# legacy-usr_interface.net
KiCad netlist of a schematic drawn in Altium Designer
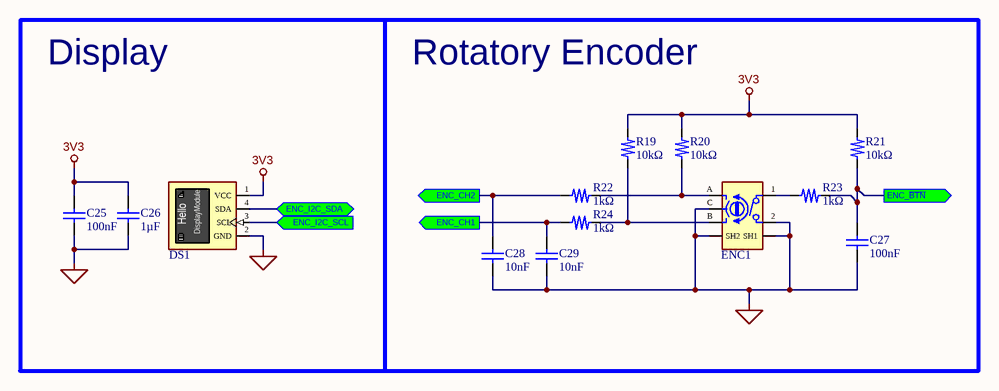
[diagram p0: legacy-usr_interface.SchDoc]

(export (version "E")
  (design (tool "Eeschema 10.0.6"))
  (components
    (comp (ref "C25")
      (value "100nF")
      (footprint "CAPC2012X135N")
      (description "50V 100nF X7R ±10% 0805 Multilayer Ceramic Capacitors MLCC - SMD/SMT ROHS")
      (fields
        (field (name "MANUFACTURER") "YAGEO")
        (field (name "MANUFACTURER PART NUMBER") "CC0805KRX7R9BB104")
      )
      (libsource (lib "Capacitors") (part "CC0805KRX7R9BB104"))
    )
    (comp (ref "C26")
      (value "1µF")
      (footprint "CAPC2012X135N")
      (description "50V 1uF X7R ±10% 0805 Multilayer Ceramic Capacitors MLCC - SMD/SMT ROHS")
      (fields
        (field (name "MANUFACTURER") "Samsung Electro-Mechanics")
        (field (name "MANUFACTURER PART NUMBER") "CL21B105KBFNNNE")
      )
      (libsource (lib "Capacitors") (part "CL21B105KBFNNNE"))
    )
    (comp (ref "C27")
      (value "100nF")
      (footprint "CAPC2012X135N")
      (description "50V 100nF X7R ±10% 0805 Multilayer Ceramic Capacitors MLCC - SMD/SMT ROHS")
      (fields
        (field (name "MANUFACTURER") "YAGEO")
        (field (name "MANUFACTURER PART NUMBER") "CC0805KRX7R9BB104")
      )
      (libsource (lib "Capacitors") (part "CC0805KRX7R9BB104"))
    )
    (comp (ref "C28")
      (value "10nF")
      (footprint "CAPC2012X135N")
      (description "50V 10nF X7R ±10% 0805 Multilayer Ceramic Capacitors MLCC - SMD/SMT ROH")
      (fields
        (field (name "MANUFACTURER") "Samsung Electro-Mechanics")
        (field (name "MANUFACTURER PART NUMBER") "CL21B103KBANNNC")
      )
      (libsource (lib "Capacitors") (part "CL21B103KBANNNC"))
    )
    (comp (ref "C29")
      (value "10nF")
      (footprint "CAPC2012X135N")
      (description "50V 10nF X7R ±10% 0805 Multilayer Ceramic Capacitors MLCC - SMD/SMT ROH")
      (fields
        (field (name "MANUFACTURER") "Samsung Electro-Mechanics")
        (field (name "MANUFACTURER PART NUMBER") "CL21B103KBANNNC")
      )
      (libsource (lib "Capacitors") (part "CL21B103KBANNNC"))
    )
    (comp (ref "DS1")
      (value "WEA012864DWPP3N00003")
      (footprint "OLEDMOD_THT_4P_27P3X27P3_I2C_MH4")
      (description "Winstar WEA012864DWPP3N00003 OLED COG 128X64 white 0.96\"on PCB I2C")
      (fields (field (name "MANUFACTURER") "Winstar Display"))
      (libsource (lib "Displays") (part "WEA012864DWPP3N00003"))
    )
    (comp (ref "ENC1")
      (value "PEC11R-4220F-S0024")
      (footprint "ROTENC_PTH_5P_SW_PEC11R")
      (description "Incremental Encoder 24 PPR 2 Bit Quadrature 5VDC at 10 mA IP40 PCB Mount 60RPM")
      (fields (field (name "MANUFACTURER") "Bourns Inc."))
      (libsource (lib "Encoders") (part "PEC11R-4220F-S0024"))
    )
    (comp (ref "R19")
      (value "10kΩ")
      (footprint "RESC2012")
      (description "Res Thick Film 0805 10K Ohm 1% 0.125W(1/8W) +/-100ppm/C Epoxy Pad SMD T/R")
      (fields
        (field (name "MANUFACTURER") "YAGEO")
        (field (name "MANUFACTURER PART NUMBER") "RC0805FR-0710KL")
      )
      (libsource (lib "Resistors") (part "RC0805FR-0710KL"))
    )
    (comp (ref "R20")
      (value "10kΩ")
      (footprint "RESC2012")
      (description "Res Thick Film 0805 10K Ohm 1% 0.125W(1/8W) +/-100ppm/C Epoxy Pad SMD T/R")
      (fields
        (field (name "MANUFACTURER") "YAGEO")
        (field (name "MANUFACTURER PART NUMBER") "RC0805FR-0710KL")
      )
      (libsource (lib "Resistors") (part "RC0805FR-0710KL"))
    )
    (comp (ref "R21")
      (value "10kΩ")
      (footprint "RESC2012")
      (description "Res Thick Film 0805 10K Ohm 1% 0.125W(1/8W) +/-100ppm/C Epoxy Pad SMD T/R")
      (fields
        (field (name "MANUFACTURER") "YAGEO")
        (field (name "MANUFACTURER PART NUMBER") "RC0805FR-0710KL")
      )
      (libsource (lib "Resistors") (part "RC0805FR-0710KL"))
    )
    (comp (ref "R22")
      (value "1kΩ")
      (footprint "RESC2012")
      (description "125Mw Thick Film Resistors 100Ppm/ 1% 4.7K 0805 Chip Resistor Surface Mount Rohs")
      (fields
        (field (name "MANUFACTURER") "YAGEO")
        (field (name "MANUFACTURER PART NUMBER") "RC0805FR-071KL")
      )
      (libsource (lib "Resistors") (part "RC0805FR-071KL"))
    )
    (comp (ref "R23")
      (value "1kΩ")
      (footprint "RESC2012")
      (description "125Mw Thick Film Resistors 100Ppm/ 1% 4.7K 0805 Chip Resistor Surface Mount Rohs")
      (fields
        (field (name "MANUFACTURER") "YAGEO")
        (field (name "MANUFACTURER PART NUMBER") "RC0805FR-071KL")
      )
      (libsource (lib "Resistors") (part "RC0805FR-071KL"))
    )
    (comp (ref "R24")
      (value "1kΩ")
      (footprint "RESC2012")
      (description "125Mw Thick Film Resistors 100Ppm/ 1% 4.7K 0805 Chip Resistor Surface Mount Rohs")
      (fields
        (field (name "MANUFACTURER") "YAGEO")
        (field (name "MANUFACTURER PART NUMBER") "RC0805FR-071KL")
      )
      (libsource (lib "Resistors") (part "RC0805FR-071KL"))
    )
  )
  (nets
    (net (code "1") (name "/ENC_CH1") (class "Default")
      (node (ref "C29") (pin "2") (pinfunction "2_2") (pintype "passive"))
      (node (ref "R24") (pin "1") (pinfunction "1_1") (pintype "passive"))
    )
    (net (code "2") (name "/ENC_CH2") (class "Default")
      (node (ref "C28") (pin "2") (pinfunction "2_2") (pintype "passive"))
      (node (ref "R22") (pin "1") (pinfunction "1_1") (pintype "passive"))
    )
    (net (code "3") (name "/ENC_I2C_SCL") (class "Default")
      (node (ref "DS1") (pin "3") (pinfunction "SCL_3") (pintype "input"))
    )
    (net (code "4") (name "/ENC_I2C_SDA") (class "Default")
      (node (ref "DS1") (pin "4") (pinfunction "SDA_4") (pintype "bidirectional"))
    )
    (net (code "5") (name "/ENC_~{BTN}") (class "Default")
      (node (ref "C27") (pin "2") (pinfunction "2_2") (pintype "passive"))
      (node (ref "R21") (pin "1") (pinfunction "1_1") (pintype "passive"))
      (node (ref "R23") (pin "2") (pinfunction "2_2") (pintype "passive"))
    )
    (net (code "6") (name "3V3") (class "Default")
      (node (ref "C25") (pin "2") (pinfunction "2_2") (pintype "passive"))
      (node (ref "C26") (pin "2") (pinfunction "2_2") (pintype "passive"))
      (node (ref "DS1") (pin "1") (pinfunction "VCC_1") (pintype "power_in"))
      (node (ref "R19") (pin "2") (pinfunction "2_2") (pintype "passive"))
      (node (ref "R20") (pin "2") (pinfunction "2_2") (pintype "passive"))
      (node (ref "R21") (pin "2") (pinfunction "2_2") (pintype "passive"))
    )
    (net (code "7") (name "DGND") (class "Default")
      (node (ref "C25") (pin "1") (pinfunction "1_1") (pintype "passive"))
      (node (ref "C26") (pin "1") (pinfunction "1_1") (pintype "passive"))
      (node (ref "C27") (pin "1") (pinfunction "1_1") (pintype "passive"))
      (node (ref "C28") (pin "1") (pinfunction "1_1") (pintype "passive"))
      (node (ref "C29") (pin "1") (pinfunction "1_1") (pintype "passive"))
      (node (ref "DS1") (pin "2") (pinfunction "GND_2") (pintype "power_in"))
      (node (ref "ENC1") (pin "2") (pinfunction "2_2") (pintype "passive"))
      (node (ref "ENC1") (pin "C") (pinfunction "COM_C") (pintype "passive"))
      (node (ref "ENC1") (pin "SH1") (pinfunction "SH1_SH1") (pintype "passive"))
      (node (ref "ENC1") (pin "SH2") (pinfunction "SH2_SH2") (pintype "passive"))
    )
    (net (code "8") (name "Net-(ENC1-Pad1)") (class "Default")
      (node (ref "ENC1") (pin "1") (pinfunction "1_1") (pintype "passive"))
      (node (ref "R23") (pin "1") (pinfunction "1_1") (pintype "passive"))
    )
    (net (code "9") (name "Net-(ENC1-PadA)") (class "Default")
      (node (ref "ENC1") (pin "A") (pinfunction "A_A") (pintype "passive"))
      (node (ref "R20") (pin "1") (pinfunction "1_1") (pintype "passive"))
      (node (ref "R22") (pin "2") (pinfunction "2_2") (pintype "passive"))
    )
    (net (code "10") (name "Net-(ENC1-PadB)") (class "Default")
      (node (ref "ENC1") (pin "B") (pinfunction "B_B") (pintype "passive"))
      (node (ref "R19") (pin "1") (pinfunction "1_1") (pintype "passive"))
      (node (ref "R24") (pin "2") (pinfunction "2_2") (pintype "passive"))
    )
  )
)
